# power_supply_linear.net
KiCad netlist of a schematic drawn in Altium Designer
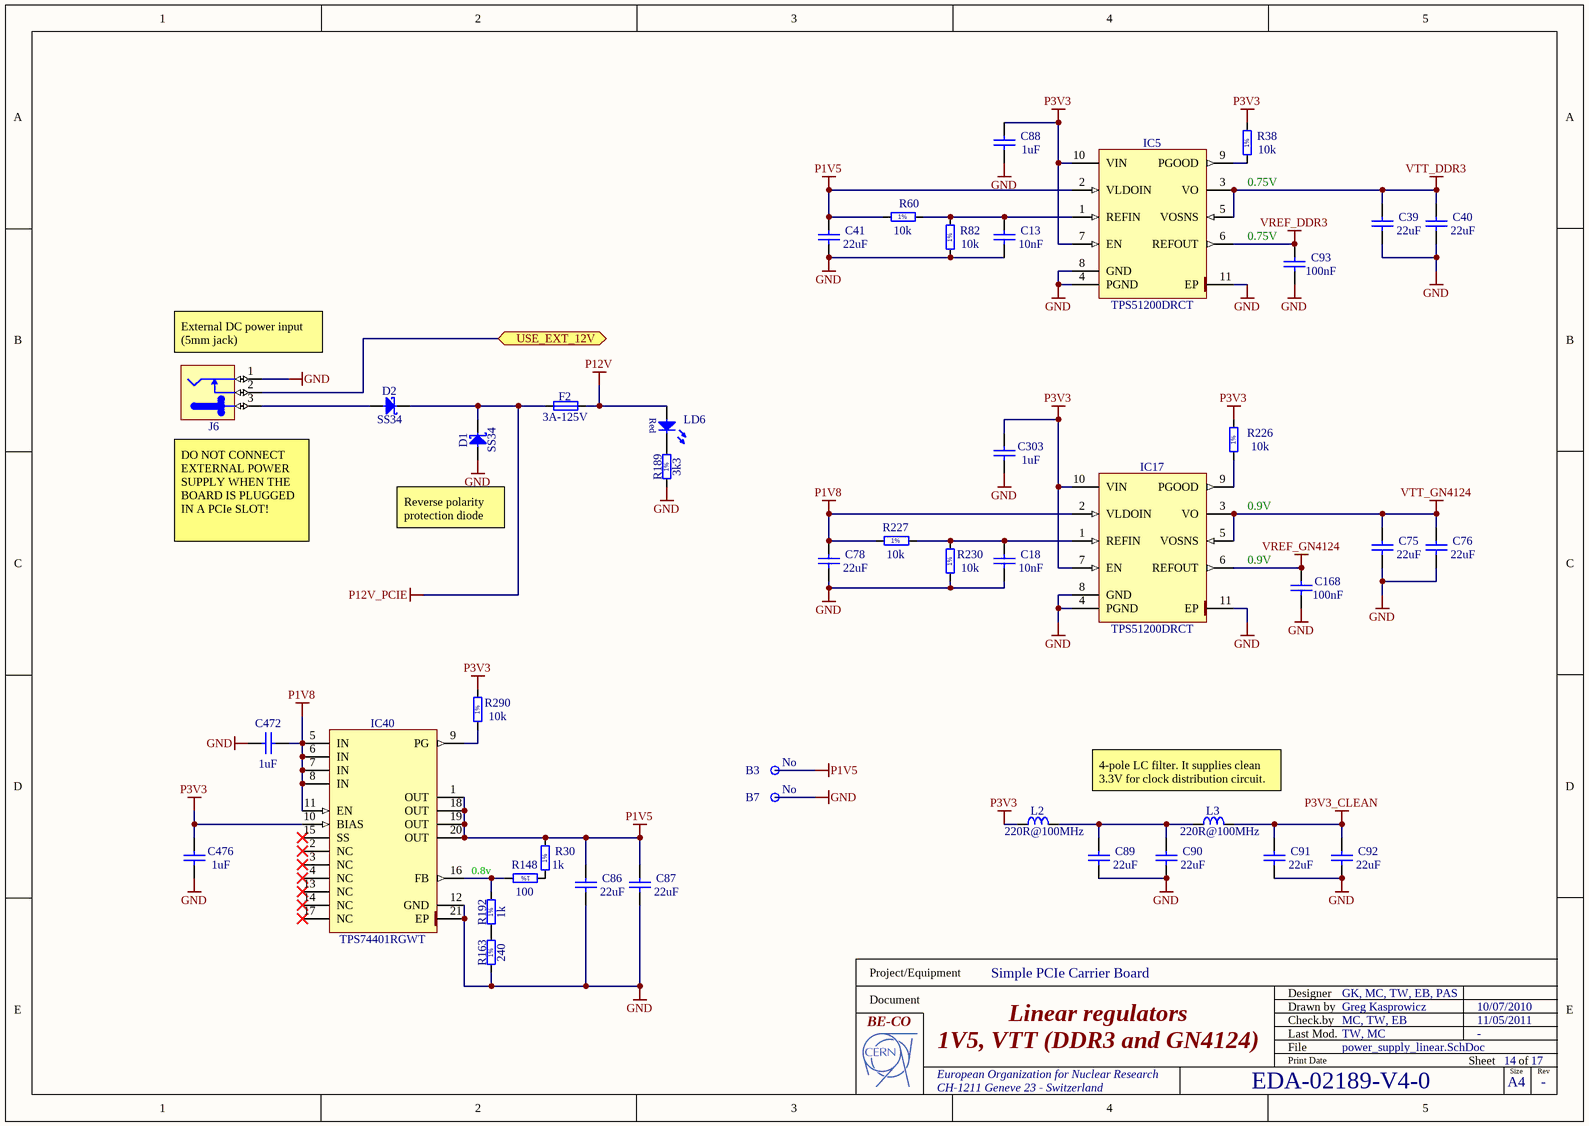
[diagram p0: power_supply_linear.SchDoc]

(export (version "E")
  (design (tool "Eeschema 10.0.6"))
  (components
    (comp (ref "B3")
      (value "Test Point")
      (footprint "VERO_20-2136")
      (description "Single Terminal Socket")
      (fields
        (field (name "PART NUMBER") "VERO_20-2136")
        (field (name "MOUNTED") "No")
        (field (name "MANUFACTURER") "VERO TECHNOLOGIES")
        (field (name "AUTHOR") "CERN DEM JLC")
      )
      (libsource (lib "Connectors") (part "Single Terminal Socket"))
    )
    (comp (ref "B7")
      (value "Test Point")
      (footprint "VERO_20-2136")
      (description "Single Terminal Socket")
      (fields
        (field (name "PART NUMBER") "VERO_20-2136")
        (field (name "MOUNTED") "No")
        (field (name "MANUFACTURER") "VERO TECHNOLOGIES")
        (field (name "AUTHOR") "CERN DEM JLC")
      )
      (libsource (lib "Connectors") (part "Single Terminal Socket"))
    )
    (comp (ref "C13")
      (value "10nF")
      (footprint "CAPC1608X87N")
      (description "Non-polarised capacitor")
      (fields
        (field (name "PART NUMBER") "CC0603_10NF_50V_10%_X7R")
        (field (name "VOLTAGE") "50V")
        (field (name "AUTHOR") "CERN DEM JLC")
      )
      (libsource (lib "Capacitors") (part "Capacitor - non polarized"))
    )
    (comp (ref "C18")
      (value "10nF")
      (footprint "CAPC1608X87N")
      (description "Non-polarised capacitor")
      (fields
        (field (name "PART NUMBER") "CC0603_10NF_50V_10%_X7R")
        (field (name "VOLTAGE") "50V")
        (field (name "AUTHOR") "CERN DEM JLC")
      )
      (libsource (lib "Capacitors") (part "Capacitor - non polarized"))
    )
    (comp (ref "C39")
      (value "22uF")
      (footprint "CAPC3216X180N")
      (description "Non-polarised capacitor")
      (fields
        (field (name "PART NUMBER") "CC1206_22UF_10V_10%_X7R")
        (field (name "VOLTAGE") "10V")
        (field (name "AUTHOR") "CERN DEM JLC")
      )
      (libsource (lib "Capacitors") (part "Capacitor - non polarized"))
    )
    (comp (ref "C40")
      (value "22uF")
      (footprint "CAPC3216X180N")
      (description "Non-polarised capacitor")
      (fields
        (field (name "PART NUMBER") "CC1206_22UF_10V_10%_X7R")
        (field (name "VOLTAGE") "10V")
        (field (name "AUTHOR") "CERN DEM JLC")
      )
      (libsource (lib "Capacitors") (part "Capacitor - non polarized"))
    )
    (comp (ref "C41")
      (value "22uF")
      (footprint "CAPC3216X180N")
      (description "Non-polarised capacitor")
      (fields
        (field (name "PART NUMBER") "CC1206_22UF_10V_10%_X7R")
        (field (name "VOLTAGE") "10V")
        (field (name "AUTHOR") "CERN DEM JLC")
      )
      (libsource (lib "Capacitors") (part "Capacitor - non polarized"))
    )
    (comp (ref "C75")
      (value "22uF")
      (footprint "CAPC3216X180N")
      (description "Non-polarised capacitor")
      (fields
        (field (name "PART NUMBER") "CC1206_22UF_10V_10%_X7R")
        (field (name "VOLTAGE") "10V")
        (field (name "AUTHOR") "CERN DEM JLC")
      )
      (libsource (lib "Capacitors") (part "Capacitor - non polarized"))
    )
    (comp (ref "C76")
      (value "22uF")
      (footprint "CAPC3216X180N")
      (description "Non-polarised capacitor")
      (fields
        (field (name "PART NUMBER") "CC1206_22UF_10V_10%_X7R")
        (field (name "VOLTAGE") "10V")
        (field (name "AUTHOR") "CERN DEM JLC")
      )
      (libsource (lib "Capacitors") (part "Capacitor - non polarized"))
    )
    (comp (ref "C78")
      (value "22uF")
      (footprint "CAPC3216X180N")
      (description "Non-polarised capacitor")
      (fields
        (field (name "PART NUMBER") "CC1206_22UF_10V_10%_X7R")
        (field (name "VOLTAGE") "10V")
        (field (name "AUTHOR") "CERN DEM JLC")
      )
      (libsource (lib "Capacitors") (part "Capacitor - non polarized"))
    )
    (comp (ref "C86")
      (value "22uF")
      (footprint "CAPC3216X180N")
      (description "Non-polarised capacitor")
      (fields
        (field (name "PART NUMBER") "CC1206_22UF_10V_10%_X7R")
        (field (name "VOLTAGE") "10V")
        (field (name "AUTHOR") "CERN DEM JLC")
      )
      (libsource (lib "Capacitors") (part "Capacitor - non polarized"))
    )
    (comp (ref "C87")
      (value "22uF")
      (footprint "CAPC3216X180N")
      (description "Non-polarised capacitor")
      (fields
        (field (name "PART NUMBER") "CC1206_22UF_10V_10%_X7R")
        (field (name "VOLTAGE") "10V")
        (field (name "AUTHOR") "CERN DEM JLC")
      )
      (libsource (lib "Capacitors") (part "Capacitor - non polarized"))
    )
    (comp (ref "C88")
      (value "1uF")
      (footprint "CAPC1608X87N")
      (description "Non-polarised capacitor")
      (fields
        (field (name "PART NUMBER") "CC0603_1UF_16V_10%_X7R")
        (field (name "VOLTAGE") "16V")
        (field (name "AUTHOR") "CERN DEM JLC")
      )
      (libsource (lib "Capacitors") (part "Capacitor - non polarized"))
    )
    (comp (ref "C89")
      (value "22uF")
      (footprint "CAPC3216X180N")
      (description "Non-polarised capacitor")
      (fields
        (field (name "PART NUMBER") "CC1206_22UF_10V_10%_X7R")
        (field (name "VOLTAGE") "10V")
        (field (name "AUTHOR") "CERN DEM JLC")
      )
      (libsource (lib "Capacitors") (part "Capacitor - non polarized"))
    )
    (comp (ref "C90")
      (value "22uF")
      (footprint "CAPC3216X180N")
      (description "Non-polarised capacitor")
      (fields
        (field (name "PART NUMBER") "CC1206_22UF_10V_10%_X7R")
        (field (name "VOLTAGE") "10V")
        (field (name "AUTHOR") "CERN DEM JLC")
      )
      (libsource (lib "Capacitors") (part "Capacitor - non polarized"))
    )
    (comp (ref "C91")
      (value "22uF")
      (footprint "CAPC3216X180N")
      (description "Non-polarised capacitor")
      (fields
        (field (name "PART NUMBER") "CC1206_22UF_10V_10%_X7R")
        (field (name "VOLTAGE") "10V")
        (field (name "AUTHOR") "CERN DEM JLC")
      )
      (libsource (lib "Capacitors") (part "Capacitor - non polarized"))
    )
    (comp (ref "C92")
      (value "22uF")
      (footprint "CAPC3216X180N")
      (description "Non-polarised capacitor")
      (fields
        (field (name "PART NUMBER") "CC1206_22UF_10V_10%_X7R")
        (field (name "VOLTAGE") "10V")
        (field (name "AUTHOR") "CERN DEM JLC")
      )
      (libsource (lib "Capacitors") (part "Capacitor - non polarized"))
    )
    (comp (ref "C93")
      (value "100nF")
      (footprint "CAPC1005X55N")
      (description "Non-polarised capacitor")
      (fields
        (field (name "PART NUMBER") "CC0402_100NF_16V_10%_X7R")
        (field (name "VOLTAGE") "16V")
        (field (name "AUTHOR") "CERN DEM JLC")
      )
      (libsource (lib "Capacitors") (part "Capacitor - non polarized"))
    )
    (comp (ref "C168")
      (value "100nF")
      (footprint "CAPC1608X87N")
      (description "Non-polarised capacitor")
      (fields
        (field (name "PART NUMBER") "CC0603_100NF_50V_10%_X7R")
        (field (name "VOLTAGE") "50V")
        (field (name "AUTHOR") "CERN DEM JLC")
      )
      (libsource (lib "Capacitors") (part "Capacitor - non polarized"))
    )
    (comp (ref "C303")
      (value "1uF")
      (footprint "CAPC1608X87N")
      (description "Non-polarised capacitor")
      (fields
        (field (name "PART NUMBER") "CC0603_1UF_16V_10%_X7R")
        (field (name "VOLTAGE") "16V")
        (field (name "AUTHOR") "CERN DEM JLC")
      )
      (libsource (lib "Capacitors") (part "Capacitor - non polarized"))
    )
    (comp (ref "C472")
      (value "1uF")
      (footprint "CAPC1608X87N")
      (description "Non-polarised capacitor")
      (fields
        (field (name "PART NUMBER") "CC0603_1UF_16V_10%_X7R")
        (field (name "VOLTAGE") "16V")
        (field (name "AUTHOR") "CERN DEM JLC")
      )
      (libsource (lib "Capacitors") (part "Capacitor - non polarized"))
    )
    (comp (ref "C476")
      (value "1uF")
      (footprint "CAPC1608X87N")
      (description "Non-polarised capacitor")
      (fields
        (field (name "PART NUMBER") "CC0603_1UF_16V_10%_X7R")
        (field (name "VOLTAGE") "16V")
        (field (name "AUTHOR") "CERN DEM JLC")
      )
      (libsource (lib "Capacitors") (part "Capacitor - non polarized"))
    )
    (comp (ref "D1")
      (value "SS34")
      (footprint "DIOM7659X265N")
      (description "Schottky Diode")
      (fields
        (field (name "VOLTAGE") "40V")
        (field (name "POWER") "3A")
        (field (name "AUTHOR") "CERN DEM JLC")
      )
      (libsource (lib "ICs And Semiconductors") (part "Diode Schottky"))
    )
    (comp (ref "D2")
      (value "SS34")
      (footprint "DIOM7659X265N")
      (description "Schottky Diode")
      (fields
        (field (name "VOLTAGE") "40V")
        (field (name "POWER") "3A")
        (field (name "AUTHOR") "CERN DEM JLC")
      )
      (libsource (lib "ICs And Semiconductors") (part "Diode Schottky"))
    )
    (comp (ref "F2")
      (value "3A-125V")
      (footprint "FUSE_LITTELFUSE_0154")
      (description "Fuse")
      (fields
        (field (name "PART NUMBER") "FUSE_LITTELFUSE_0154003.DR")
        (field (name "MANUFACTURER") "LITTELFUSE")
        (field (name "AUTHOR") "CERN DEM JMW")
      )
      (libsource (lib "Eletro-mechanical") (part "Fuse"))
    )
    (comp (ref "IC5")
      (value "TPS51200DRCT")
      (footprint "SON50P300X300X100-11N-R175X250")
      (description "Sink/Source DDR Termination Regulator")
      (fields (field (name "MANUFACTURER") "TEXAS INSTRUMENTS") (field (name "AUTHOR") "CERN DEM JLC"))
      (libsource (lib "ICs And Semiconductors") (part "TPS51200DRC"))
    )
    (comp (ref "IC17")
      (value "TPS51200DRCT")
      (footprint "SON50P300X300X100-11N-R175X250")
      (description "Sink/Source DDR Termination Regulator")
      (fields (field (name "MANUFACTURER") "TEXAS INSTRUMENTS") (field (name "AUTHOR") "CERN DEM JLC"))
      (libsource (lib "ICs And Semiconductors") (part "TPS51200DRC"))
    )
    (comp (ref "IC40")
      (value "TPS74401RGWT")
      (footprint "QFN65P500X500X100-21N-S325")
      (description "Single Output LDO, 3.0A, Adj.(0.8 to 3.3V), Fast Transient Response, Programmable SoftStart")
      (fields (field (name "MANUFACTURER") "TEXAS INSTRUMENTS") (field (name "AUTHOR") "CERN DEM JLC"))
      (libsource (lib "ICs And Semiconductors") (part "TPS74401RGW"))
    )
    (comp (ref "J6")
      (value "Jack")
      (footprint "LUMBERG_161314")
      (description "24V /3. 5A, 2.1mm Diameter Pin, SMD DC Power Supply Connector With  Break Contact")
      (fields
        (field (name "PART NUMBER") "LUMBERG_161314")
        (field (name "MANUFACTURER") "LUMBERG")
        (field (name "AUTHOR") "CERN DEM JLC")
      )
      (libsource (lib "Connectors") (part "LUMBERG_161314"))
    )
    (comp (ref "L2")
      (value "220R@100MHz")
      (footprint "INDC2012X105N")
      (description "Inductor")
      (fields
        (field (name "PART NUMBER") "IND0805_MURATA_BLM21PG221SN1D")
        (field (name "POWER") "2A")
        (field (name "AUTHOR") "CERN DEM JLC")
      )
      (libsource (lib "Inductors & Transformers") (part "Inductor"))
    )
    (comp (ref "L3")
      (value "220R@100MHz")
      (footprint "INDC2012X105N")
      (description "Inductor")
      (fields
        (field (name "PART NUMBER") "IND0805_MURATA_BLM21PG221SN1D")
        (field (name "POWER") "2A")
        (field (name "AUTHOR") "CERN DEM JLC")
      )
      (libsource (lib "Inductors & Transformers") (part "Inductor"))
    )
    (comp (ref "LD6")
      (value "Red")
      (footprint "LEDC1608X80N_RED")
      (description "LED Red 1C 2A")
      (fields
        (field (name "PART NUMBER") "LED_ROHM_SML-311UTT86K")
        (field (name "MANUFACTURER") "ROHM")
        (field (name "AUTHOR") "CERN DEM JLC")
      )
      (libsource (lib "ICs And Semiconductors") (part "LED Red 1C 2A"))
    )
    (comp (ref "R30")
      (value "1k")
      (footprint "RESC1608X55N")
      (description "Resistor - 1%")
      (fields
        (field (name "PART NUMBER") "R0603_1K_1%_0.1W_100PPM")
        (field (name "POWER") "0.1W")
        (field (name "AUTHOR") "CERN DEM JLC")
      )
      (libsource (lib "Resistors") (part "Resistor - 1%"))
    )
    (comp (ref "R38")
      (value "10k")
      (footprint "RESC1608X55N")
      (description "Resistor - 1%")
      (fields
        (field (name "PART NUMBER") "R0603_10K_1%_0.1W_100PPM")
        (field (name "POWER") "0.1W")
        (field (name "AUTHOR") "CERN DEM JLC")
      )
      (libsource (lib "Resistors") (part "Resistor - 1%"))
    )
    (comp (ref "R60")
      (value "10k")
      (footprint "RESC1608X55N")
      (description "Resistor - 1%")
      (fields
        (field (name "PART NUMBER") "R0603_10K_1%_0.1W_100PPM")
        (field (name "POWER") "0.1W")
        (field (name "AUTHOR") "CERN DEM JLC")
      )
      (libsource (lib "Resistors") (part "Resistor - 1%"))
    )
    (comp (ref "R82")
      (value "10k")
      (footprint "RESC1608X55N")
      (description "Resistor - 1%")
      (fields
        (field (name "PART NUMBER") "R0603_10K_1%_0.1W_100PPM")
        (field (name "POWER") "0.1W")
        (field (name "AUTHOR") "CERN DEM JLC")
      )
      (libsource (lib "Resistors") (part "Resistor - 1%"))
    )
    (comp (ref "R148")
      (value "100")
      (footprint "RESC1608X55N")
      (description "Resistor - 1%")
      (fields
        (field (name "PART NUMBER") "R0603_100R_1%_0.1W_100PPM")
        (field (name "POWER") "0.1W")
        (field (name "AUTHOR") "CERN DEM JLC")
      )
      (libsource (lib "Resistors") (part "Resistor - 1%"))
    )
    (comp (ref "R163")
      (value "240")
      (footprint "RESC1608X55N")
      (description "Resistor - 1%")
      (fields
        (field (name "PART NUMBER") "R0603_240R_1%_0.1W_100PPM")
        (field (name "POWER") "0.1W")
        (field (name "AUTHOR") "CERN DEM JLC")
      )
      (libsource (lib "Resistors") (part "Resistor - 1%"))
    )
    (comp (ref "R189")
      (value "3k3")
      (footprint "RESC1608X55N")
      (description "Resistor - 1%")
      (fields
        (field (name "PART NUMBER") "R0603_3K3_1%_0.1W_100PPM")
        (field (name "POWER") "0.1W")
        (field (name "AUTHOR") "CERN DEM JLC")
      )
      (libsource (lib "Resistors") (part "Resistor - 1%"))
    )
    (comp (ref "R192")
      (value "1k")
      (footprint "RESC1608X55N")
      (description "Resistor - 1%")
      (fields
        (field (name "PART NUMBER") "R0603_1K_1%_0.1W_100PPM")
        (field (name "POWER") "0.1W")
        (field (name "AUTHOR") "CERN DEM JLC")
      )
      (libsource (lib "Resistors") (part "Resistor - 1%"))
    )
    (comp (ref "R226")
      (value "10k")
      (footprint "RESC1608X55N")
      (description "Resistor - 1%")
      (fields
        (field (name "PART NUMBER") "R0603_10K_1%_0.1W_100PPM")
        (field (name "POWER") "0.1W")
        (field (name "AUTHOR") "CERN DEM JLC")
      )
      (libsource (lib "Resistors") (part "Resistor - 1%"))
    )
    (comp (ref "R227")
      (value "10k")
      (footprint "RESC1608X55N")
      (description "Resistor - 1%")
      (fields
        (field (name "PART NUMBER") "R0603_10K_1%_0.1W_100PPM")
        (field (name "POWER") "0.1W")
        (field (name "AUTHOR") "CERN DEM JLC")
      )
      (libsource (lib "Resistors") (part "Resistor - 1%"))
    )
    (comp (ref "R230")
      (value "10k")
      (footprint "RESC1608X55N")
      (description "Resistor - 1%")
      (fields
        (field (name "PART NUMBER") "R0603_10K_1%_0.1W_100PPM")
        (field (name "POWER") "0.1W")
        (field (name "AUTHOR") "CERN DEM JLC")
      )
      (libsource (lib "Resistors") (part "Resistor - 1%"))
    )
    (comp (ref "R290")
      (value "10k")
      (footprint "RESC1608X55N")
      (description "Resistor - 1%")
      (fields
        (field (name "PART NUMBER") "R0603_10K_1%_0.1W_100PPM")
        (field (name "POWER") "0.1W")
        (field (name "AUTHOR") "CERN DEM JLC")
      )
      (libsource (lib "Resistors") (part "Resistor - 1%"))
    )
  )
  (nets
    (net (code "1") (name "/USE_EXT_12V") (class "Default")
      (node (ref "J6") (pin "2") (pinfunction "2_2") (pintype "bidirectional"))
    )
    (net (code "2") (name "GND") (class "Default")
      (node (ref "B7") (pin "1") (pinfunction "1_1") (pintype "bidirectional"))
      (node (ref "C13") (pin "1") (pinfunction "1_1") (pintype "passive"))
      (node (ref "C168") (pin "1") (pinfunction "1_1") (pintype "passive"))
      (node (ref "C18") (pin "1") (pinfunction "1_1") (pintype "passive"))
      (node (ref "C303") (pin "1") (pinfunction "1_1") (pintype "passive"))
      (node (ref "C39") (pin "1") (pinfunction "1_1") (pintype "passive"))
      (node (ref "C40") (pin "1") (pinfunction "1_1") (pintype "passive"))
      (node (ref "C41") (pin "1") (pinfunction "1_1") (pintype "passive"))
      (node (ref "C472") (pin "1") (pinfunction "1_1") (pintype "passive"))
      (node (ref "C476") (pin "1") (pinfunction "1_1") (pintype "passive"))
      (node (ref "C75") (pin "1") (pinfunction "1_1") (pintype "passive"))
      (node (ref "C76") (pin "1") (pinfunction "1_1") (pintype "passive"))
      (node (ref "C78") (pin "1") (pinfunction "1_1") (pintype "passive"))
      (node (ref "C86") (pin "1") (pinfunction "1_1") (pintype "passive"))
      (node (ref "C87") (pin "1") (pinfunction "1_1") (pintype "passive"))
      (node (ref "C88") (pin "1") (pinfunction "1_1") (pintype "passive"))
      (node (ref "C89") (pin "1") (pinfunction "1_1") (pintype "passive"))
      (node (ref "C90") (pin "1") (pinfunction "1_1") (pintype "passive"))
      (node (ref "C91") (pin "1") (pinfunction "1_1") (pintype "passive"))
      (node (ref "C92") (pin "1") (pinfunction "1_1") (pintype "passive"))
      (node (ref "C93") (pin "1") (pinfunction "1_1") (pintype "passive"))
      (node (ref "D1") (pin "2") (pinfunction "A_2") (pintype "passive"))
      (node (ref "IC17") (pin "11") (pinfunction "EP_11") (pintype "power_in"))
      (node (ref "IC17") (pin "4") (pinfunction "PGND_4") (pintype "power_in"))
      (node (ref "IC17") (pin "8") (pinfunction "GND_8") (pintype "power_in"))
      (node (ref "IC40") (pin "12") (pinfunction "GND_12") (pintype "power_in"))
      (node (ref "IC40") (pin "21") (pinfunction "EP_21") (pintype "power_in"))
      (node (ref "IC5") (pin "11") (pinfunction "EP_11") (pintype "power_in"))
      (node (ref "IC5") (pin "4") (pinfunction "PGND_4") (pintype "power_in"))
      (node (ref "IC5") (pin "8") (pinfunction "GND_8") (pintype "power_in"))
      (node (ref "J6") (pin "1") (pinfunction "1_1") (pintype "bidirectional"))
      (node (ref "R163") (pin "1") (pinfunction "1_1") (pintype "passive"))
      (node (ref "R189") (pin "1") (pinfunction "1_1") (pintype "passive"))
      (node (ref "R230") (pin "1") (pinfunction "1_1") (pintype "passive"))
      (node (ref "R82") (pin "1") (pinfunction "1_1") (pintype "passive"))
    )
    (net (code "3") (name "Net-(C89-Pad2)") (class "Default")
      (node (ref "C89") (pin "2") (pinfunction "2_2") (pintype "passive"))
      (node (ref "C90") (pin "2") (pinfunction "2_2") (pintype "passive"))
      (node (ref "L2") (pin "2") (pinfunction "2_2") (pintype "passive"))
      (node (ref "L3") (pin "1") (pinfunction "1_1") (pintype "passive"))
    )
    (net (code "4") (name "Net-(D2-A)") (class "Default")
      (node (ref "D2") (pin "2") (pinfunction "A_2") (pintype "passive"))
      (node (ref "J6") (pin "3") (pinfunction "3_3") (pintype "bidirectional"))
    )
    (net (code "5") (name "Net-(IC5-PGOOD)") (class "Default")
      (node (ref "IC5") (pin "9") (pinfunction "PGOOD_9") (pintype "output"))
      (node (ref "R38") (pin "1") (pinfunction "1_1") (pintype "passive"))
    )
    (net (code "6") (name "Net-(IC5-REFIN)") (class "Default")
      (node (ref "C13") (pin "2") (pinfunction "2_2") (pintype "passive"))
      (node (ref "IC5") (pin "1") (pinfunction "REFIN_1") (pintype "input"))
      (node (ref "R60") (pin "2") (pinfunction "2_2") (pintype "passive"))
      (node (ref "R82") (pin "2") (pinfunction "2_2") (pintype "passive"))
    )
    (net (code "7") (name "Net-(IC17-PGOOD)") (class "Default")
      (node (ref "IC17") (pin "9") (pinfunction "PGOOD_9") (pintype "output"))
      (node (ref "R226") (pin "1") (pinfunction "1_1") (pintype "passive"))
    )
    (net (code "8") (name "Net-(IC17-REFIN)") (class "Default")
      (node (ref "C18") (pin "2") (pinfunction "2_2") (pintype "passive"))
      (node (ref "IC17") (pin "1") (pinfunction "REFIN_1") (pintype "input"))
      (node (ref "R227") (pin "2") (pinfunction "2_2") (pintype "passive"))
      (node (ref "R230") (pin "2") (pinfunction "2_2") (pintype "passive"))
    )
    (net (code "9") (name "Net-(IC40-FB)") (class "Default")
      (node (ref "IC40") (pin "16") (pinfunction "FB_16") (pintype "output"))
      (node (ref "R148") (pin "2") (pinfunction "2_2") (pintype "passive"))
      (node (ref "R192") (pin "2") (pinfunction "2_2") (pintype "passive"))
    )
    (net (code "10") (name "Net-(IC40-PG)") (class "Default")
      (node (ref "IC40") (pin "9") (pinfunction "PG_9") (pintype "output"))
      (node (ref "R290") (pin "1") (pinfunction "1_1") (pintype "passive"))
    )
    (net (code "11") (name "Net-(LD6-C)") (class "Default")
      (node (ref "LD6") (pin "1") (pinfunction "C_1") (pintype "passive"))
      (node (ref "R189") (pin "2") (pinfunction "2_2") (pintype "passive"))
    )
    (net (code "12") (name "Net-(R148-Pad1)") (class "Default")
      (node (ref "R148") (pin "1") (pinfunction "1_1") (pintype "passive"))
      (node (ref "R30") (pin "1") (pinfunction "1_1") (pintype "passive"))
    )
    (net (code "13") (name "Net-(R163-Pad2)") (class "Default")
      (node (ref "R163") (pin "2") (pinfunction "2_2") (pintype "passive"))
      (node (ref "R192") (pin "1") (pinfunction "1_1") (pintype "passive"))
    )
    (net (code "14") (name "P1V5") (class "Default")
      (node (ref "B3") (pin "1") (pinfunction "1_1") (pintype "bidirectional"))
      (node (ref "C41") (pin "2") (pinfunction "2_2") (pintype "passive"))
      (node (ref "C86") (pin "2") (pinfunction "2_2") (pintype "passive"))
      (node (ref "C87") (pin "2") (pinfunction "2_2") (pintype "passive"))
      (node (ref "IC40") (pin "1") (pinfunction "OUT_1") (pintype "power_in"))
      (node (ref "IC40") (pin "18") (pinfunction "OUT_18") (pintype "power_in"))
      (node (ref "IC40") (pin "19") (pinfunction "OUT_19") (pintype "power_in"))
      (node (ref "IC40") (pin "20") (pinfunction "OUT_20") (pintype "power_in"))
      (node (ref "IC5") (pin "2") (pinfunction "VLDOIN_2") (pintype "input"))
      (node (ref "R30") (pin "2") (pinfunction "2_2") (pintype "passive"))
      (node (ref "R60") (pin "1") (pinfunction "1_1") (pintype "passive"))
    )
    (net (code "15") (name "P1V8") (class "Default")
      (node (ref "C472") (pin "2") (pinfunction "2_2") (pintype "passive"))
      (node (ref "C78") (pin "2") (pinfunction "2_2") (pintype "passive"))
      (node (ref "IC17") (pin "2") (pinfunction "VLDOIN_2") (pintype "input"))
      (node (ref "IC40") (pin "11") (pinfunction "EN_11") (pintype "input"))
      (node (ref "IC40") (pin "5") (pinfunction "IN_5") (pintype "power_in"))
      (node (ref "IC40") (pin "6") (pinfunction "IN_6") (pintype "power_in"))
      (node (ref "IC40") (pin "7") (pinfunction "IN_7") (pintype "power_in"))
      (node (ref "IC40") (pin "8") (pinfunction "IN_8") (pintype "power_in"))
      (node (ref "R227") (pin "1") (pinfunction "1_1") (pintype "passive"))
    )
    (net (code "16") (name "P3V3") (class "Default")
      (node (ref "C303") (pin "2") (pinfunction "2_2") (pintype "passive"))
      (node (ref "C476") (pin "2") (pinfunction "2_2") (pintype "passive"))
      (node (ref "C88") (pin "2") (pinfunction "2_2") (pintype "passive"))
      (node (ref "IC17") (pin "10") (pinfunction "VIN_10") (pintype "power_in"))
      (node (ref "IC17") (pin "7") (pinfunction "EN_7") (pintype "input"))
      (node (ref "IC40") (pin "10") (pinfunction "BIAS_10") (pintype "input"))
      (node (ref "IC5") (pin "10") (pinfunction "VIN_10") (pintype "power_in"))
      (node (ref "IC5") (pin "7") (pinfunction "EN_7") (pintype "input"))
      (node (ref "L2") (pin "1") (pinfunction "1_1") (pintype "passive"))
      (node (ref "R226") (pin "2") (pinfunction "2_2") (pintype "passive"))
      (node (ref "R290") (pin "2") (pinfunction "2_2") (pintype "passive"))
      (node (ref "R38") (pin "2") (pinfunction "2_2") (pintype "passive"))
    )
    (net (code "17") (name "P3V3_CLEAN") (class "Default")
      (node (ref "C91") (pin "2") (pinfunction "2_2") (pintype "passive"))
      (node (ref "C92") (pin "2") (pinfunction "2_2") (pintype "passive"))
      (node (ref "L3") (pin "2") (pinfunction "2_2") (pintype "passive"))
    )
    (net (code "18") (name "P12V") (class "Default")
      (node (ref "F2") (pin "2") (pinfunction "2_2") (pintype "passive"))
      (node (ref "LD6") (pin "2") (pinfunction "A_2") (pintype "passive"))
    )
    (net (code "19") (name "P12V_PCIE") (class "Default")
      (node (ref "D1") (pin "1") (pinfunction "C_1") (pintype "passive"))
      (node (ref "D2") (pin "1") (pinfunction "C_1") (pintype "passive"))
      (node (ref "F2") (pin "1") (pinfunction "1_1") (pintype "passive"))
    )
    (net (code "20") (name "VREF_DDR3") (class "Default")
      (node (ref "C93") (pin "2") (pinfunction "2_2") (pintype "passive"))
      (node (ref "IC5") (pin "6") (pinfunction "REFOUT_6") (pintype "output"))
    )
    (net (code "21") (name "VREF_GN4124") (class "Default")
      (node (ref "C168") (pin "2") (pinfunction "2_2") (pintype "passive"))
      (node (ref "IC17") (pin "6") (pinfunction "REFOUT_6") (pintype "output"))
    )
    (net (code "22") (name "VTT_DDR3") (class "Default")
      (node (ref "C39") (pin "2") (pinfunction "2_2") (pintype "passive"))
      (node (ref "C40") (pin "2") (pinfunction "2_2") (pintype "passive"))
      (node (ref "IC5") (pin "3") (pinfunction "VO_3") (pintype "power_in"))
      (node (ref "IC5") (pin "5") (pinfunction "VOSNS_5") (pintype "input"))
    )
    (net (code "23") (name "VTT_GN4124") (class "Default")
      (node (ref "C75") (pin "2") (pinfunction "2_2") (pintype "passive"))
      (node (ref "C76") (pin "2") (pinfunction "2_2") (pintype "passive"))
      (node (ref "IC17") (pin "3") (pinfunction "VO_3") (pintype "power_in"))
      (node (ref "IC17") (pin "5") (pinfunction "VOSNS_5") (pintype "input"))
    )
    (net (code "24") (name "unconnected-(IC40-NC-Pad2)") (class "Default")
      (node (ref "IC40") (pin "2") (pinfunction "NC_2") (pintype "passive+no_connect"))
    )
    (net (code "25") (name "unconnected-(IC40-NC-Pad3)") (class "Default")
      (node (ref "IC40") (pin "3") (pinfunction "NC_3") (pintype "passive+no_connect"))
    )
    (net (code "26") (name "unconnected-(IC40-NC-Pad4)") (class "Default")
      (node (ref "IC40") (pin "4") (pinfunction "NC_4") (pintype "passive+no_connect"))
    )
    (net (code "27") (name "unconnected-(IC40-NC-Pad13)") (class "Default")
      (node (ref "IC40") (pin "13") (pinfunction "NC_13") (pintype "passive+no_connect"))
    )
    (net (code "28") (name "unconnected-(IC40-NC-Pad14)") (class "Default")
      (node (ref "IC40") (pin "14") (pinfunction "NC_14") (pintype "passive+no_connect"))
    )
    (net (code "29") (name "unconnected-(IC40-NC-Pad17)") (class "Default")
      (node (ref "IC40") (pin "17") (pinfunction "NC_17") (pintype "passive+no_connect"))
    )
    (net (code "30") (name "unconnected-(IC40-SS-Pad15)") (class "Default")
      (node (ref "IC40") (pin "15") (pinfunction "SS_15") (pintype "passive+no_connect"))
    )
  )
)
